# I2C_Switch.net
KiCad netlist of a schematic drawn in Altium Designer
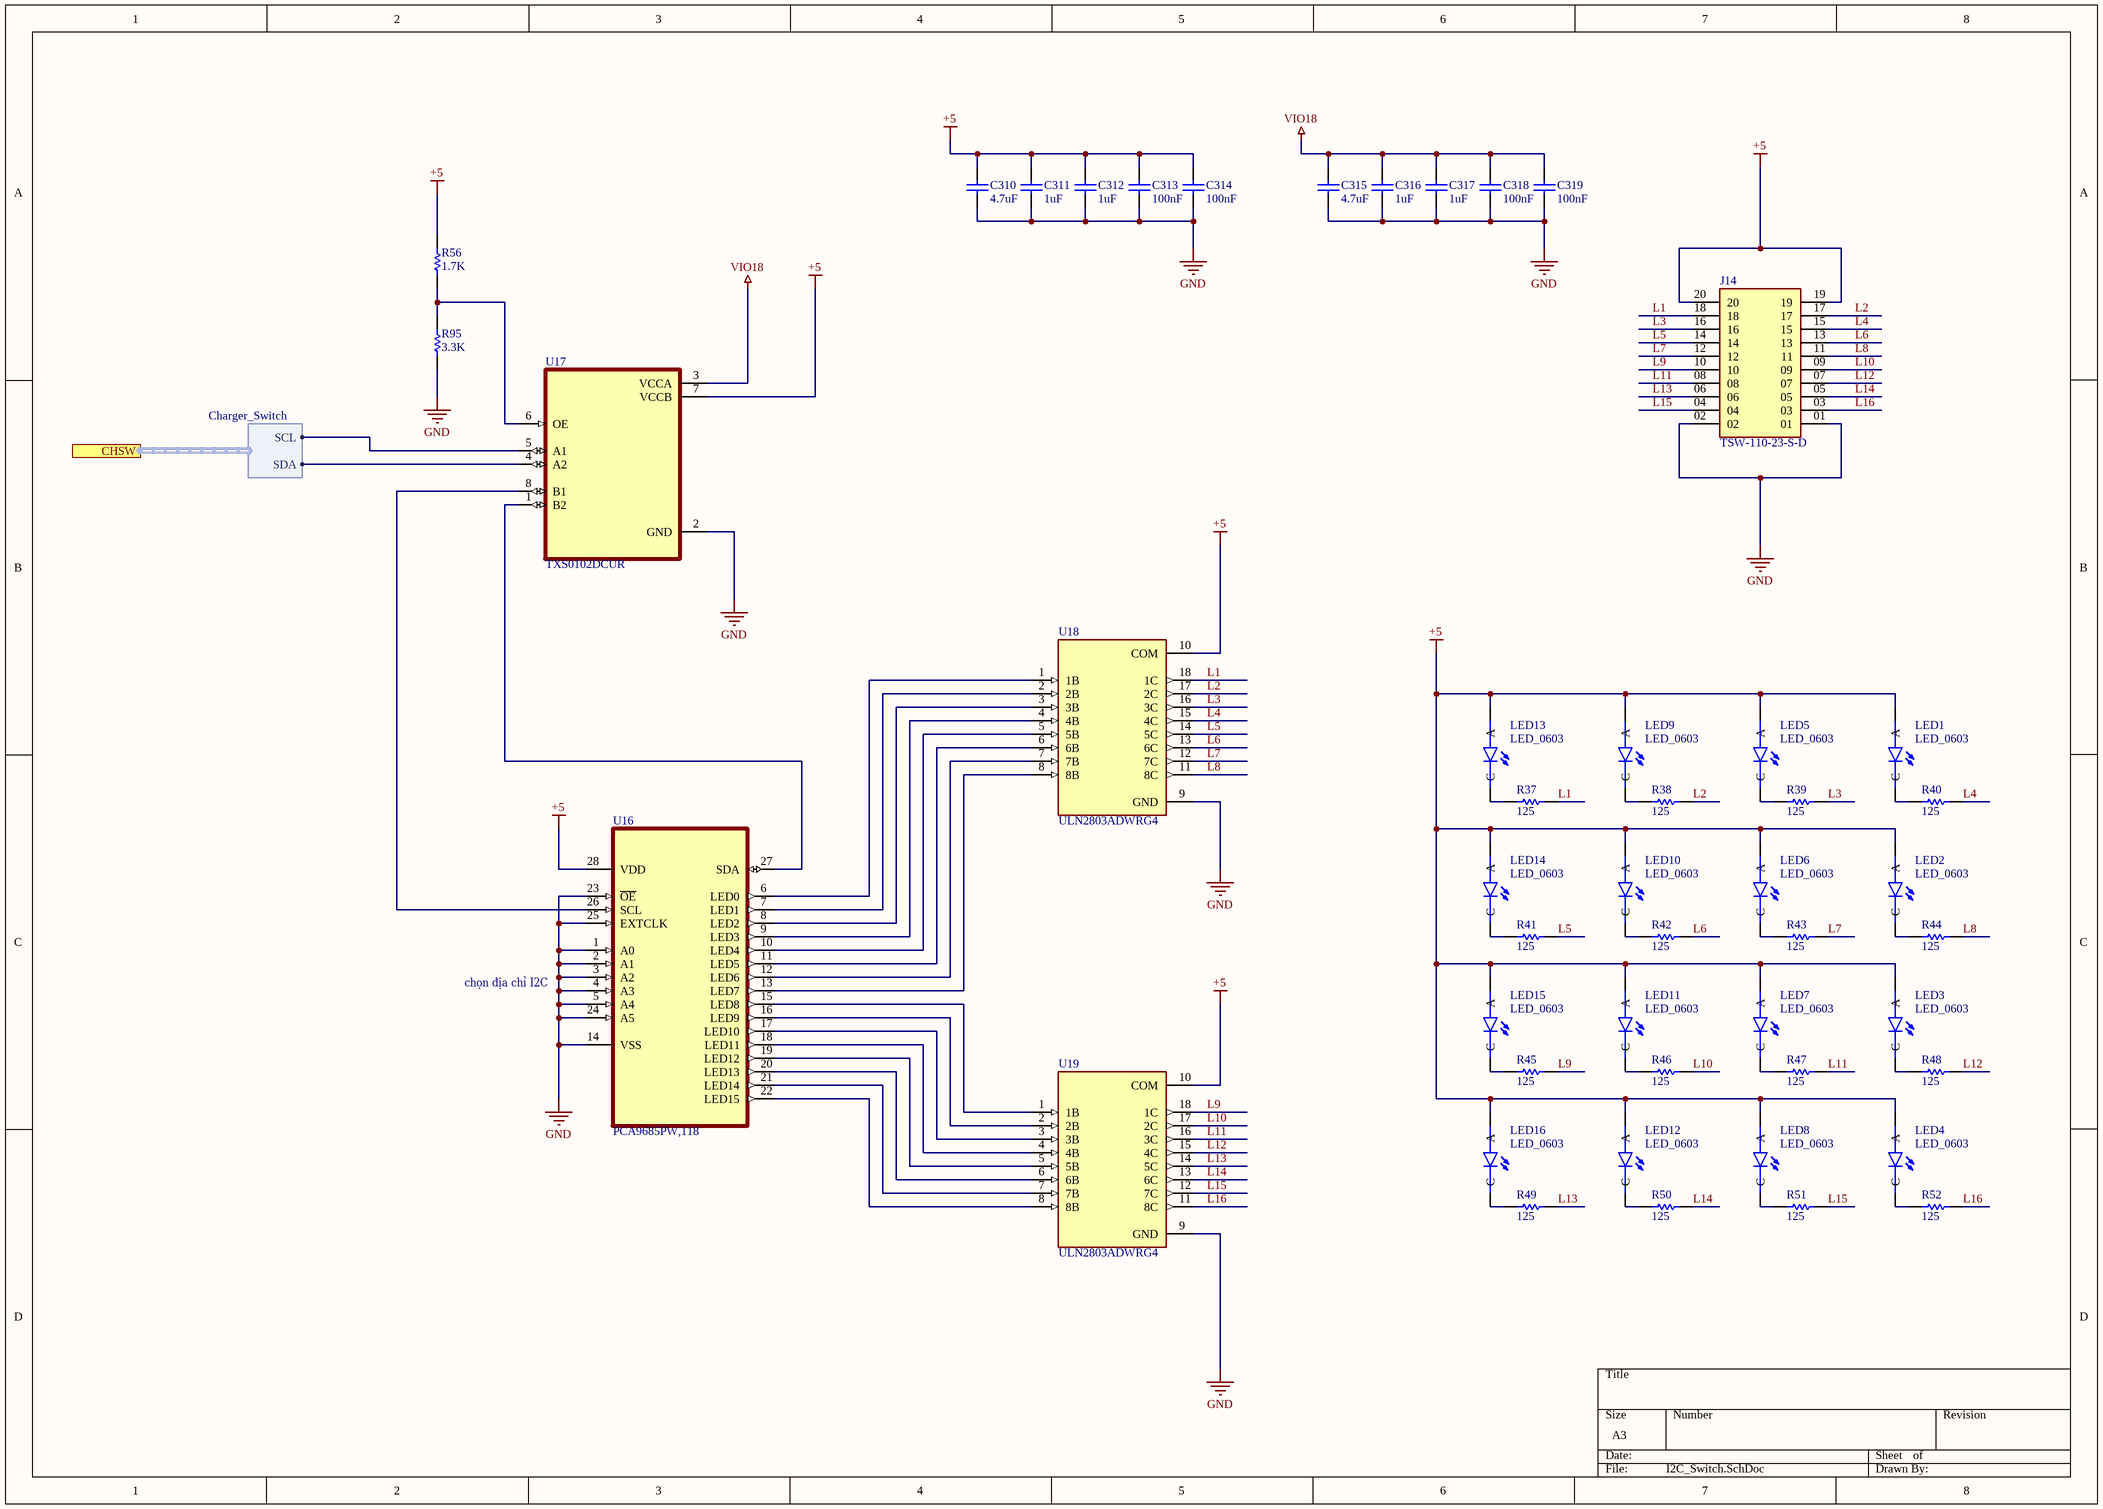
[diagram p0: I2C_Switch.SchDoc]

(export (version "E")
  (design (tool "Eeschema 10.0.6"))
  (components
    (comp (ref "C310")
      (value "4.7uF")
      (footprint "C0805")
      (fields (field (name "Comment") "C0805"))
      (libsource (lib "kit") (part "C0805"))
    )
    (comp (ref "C311")
      (value "1uF")
      (footprint "C0805")
      (fields (field (name "Comment") "C0805"))
      (libsource (lib "kit") (part "C0805"))
    )
    (comp (ref "C312")
      (value "1uF")
      (footprint "C0805")
      (fields (field (name "Comment") "C0805"))
      (libsource (lib "kit") (part "C0805"))
    )
    (comp (ref "C313")
      (value "100nF")
      (footprint "C0603")
      (fields (field (name "Comment") "C0603"))
      (libsource (lib "kit") (part "C0603"))
    )
    (comp (ref "C314")
      (value "100nF")
      (footprint "C0603")
      (fields (field (name "Comment") "C0603"))
      (libsource (lib "kit") (part "C0603"))
    )
    (comp (ref "C315")
      (value "4.7uF")
      (footprint "C0805")
      (fields (field (name "Comment") "C0805"))
      (libsource (lib "kit") (part "C0805"))
    )
    (comp (ref "C316")
      (value "1uF")
      (footprint "C0805")
      (fields (field (name "Comment") "C0805"))
      (libsource (lib "kit") (part "C0805"))
    )
    (comp (ref "C317")
      (value "1uF")
      (footprint "C0805")
      (fields (field (name "Comment") "C0805"))
      (libsource (lib "kit") (part "C0805"))
    )
    (comp (ref "C318")
      (value "100nF")
      (footprint "C0603")
      (fields (field (name "Comment") "C0603"))
      (libsource (lib "kit") (part "C0603"))
    )
    (comp (ref "C319")
      (value "100nF")
      (footprint "C0603")
      (fields (field (name "Comment") "C0603"))
      (libsource (lib "kit") (part "C0603"))
    )
    (comp (ref "J14")
      (value "TSW-110-23-S-D")
      (footprint "SAMTEC_TSW-110-23-S-D")
      (description "TSW Series .100 Terminal Strip")
      (libsource (lib "kit") (part "TSW-110-23-S-D"))
    )
    (comp (ref "LED1")
      (value "LED_0603")
      (footprint "LED_0603")
      (description "LED SMD")
      (libsource (lib "kit") (part "LED_0603"))
    )
    (comp (ref "LED2")
      (value "LED_0603")
      (footprint "LED_0603")
      (description "LED SMD")
      (libsource (lib "kit") (part "LED_0603"))
    )
    (comp (ref "LED3")
      (value "LED_0603")
      (footprint "LED_0603")
      (description "LED SMD")
      (libsource (lib "kit") (part "LED_0603"))
    )
    (comp (ref "LED4")
      (value "LED_0603")
      (footprint "LED_0603")
      (description "LED SMD")
      (libsource (lib "kit") (part "LED_0603"))
    )
    (comp (ref "LED5")
      (value "LED_0603")
      (footprint "LED_0603")
      (description "LED SMD")
      (libsource (lib "kit") (part "LED_0603"))
    )
    (comp (ref "LED6")
      (value "LED_0603")
      (footprint "LED_0603")
      (description "LED SMD")
      (libsource (lib "kit") (part "LED_0603"))
    )
    (comp (ref "LED7")
      (value "LED_0603")
      (footprint "LED_0603")
      (description "LED SMD")
      (libsource (lib "kit") (part "LED_0603"))
    )
    (comp (ref "LED8")
      (value "LED_0603")
      (footprint "LED_0603")
      (description "LED SMD")
      (libsource (lib "kit") (part "LED_0603"))
    )
    (comp (ref "LED9")
      (value "LED_0603")
      (footprint "LED_0603")
      (description "LED SMD")
      (libsource (lib "kit") (part "LED_0603"))
    )
    (comp (ref "LED10")
      (value "LED_0603")
      (footprint "LED_0603")
      (description "LED SMD")
      (libsource (lib "kit") (part "LED_0603"))
    )
    (comp (ref "LED11")
      (value "LED_0603")
      (footprint "LED_0603")
      (description "LED SMD")
      (libsource (lib "kit") (part "LED_0603"))
    )
    (comp (ref "LED12")
      (value "LED_0603")
      (footprint "LED_0603")
      (description "LED SMD")
      (libsource (lib "kit") (part "LED_0603"))
    )
    (comp (ref "LED13")
      (value "LED_0603")
      (footprint "LED_0603")
      (description "LED SMD")
      (libsource (lib "kit") (part "LED_0603"))
    )
    (comp (ref "LED14")
      (value "LED_0603")
      (footprint "LED_0603")
      (description "LED SMD")
      (libsource (lib "kit") (part "LED_0603"))
    )
    (comp (ref "LED15")
      (value "LED_0603")
      (footprint "LED_0603")
      (description "LED SMD")
      (libsource (lib "kit") (part "LED_0603"))
    )
    (comp (ref "LED16")
      (value "LED_0603")
      (footprint "LED_0603")
      (description "LED SMD")
      (libsource (lib "kit") (part "LED_0603"))
    )
    (comp (ref "R37")
      (value "125")
      (footprint "R0603")
      (fields (field (name "Comment") "R0603"))
      (libsource (lib "kit") (part "R0603"))
    )
    (comp (ref "R38")
      (value "125")
      (footprint "R0603")
      (fields (field (name "Comment") "R0603"))
      (libsource (lib "kit") (part "R0603"))
    )
    (comp (ref "R39")
      (value "125")
      (footprint "R0603")
      (fields (field (name "Comment") "R0603"))
      (libsource (lib "kit") (part "R0603"))
    )
    (comp (ref "R40")
      (value "125")
      (footprint "R0603")
      (fields (field (name "Comment") "R0603"))
      (libsource (lib "kit") (part "R0603"))
    )
    (comp (ref "R41")
      (value "125")
      (footprint "R0603")
      (fields (field (name "Comment") "R0603"))
      (libsource (lib "kit") (part "R0603"))
    )
    (comp (ref "R42")
      (value "125")
      (footprint "R0603")
      (fields (field (name "Comment") "R0603"))
      (libsource (lib "kit") (part "R0603"))
    )
    (comp (ref "R43")
      (value "125")
      (footprint "R0603")
      (fields (field (name "Comment") "R0603"))
      (libsource (lib "kit") (part "R0603"))
    )
    (comp (ref "R44")
      (value "125")
      (footprint "R0603")
      (fields (field (name "Comment") "R0603"))
      (libsource (lib "kit") (part "R0603"))
    )
    (comp (ref "R45")
      (value "125")
      (footprint "R0603")
      (fields (field (name "Comment") "R0603"))
      (libsource (lib "kit") (part "R0603"))
    )
    (comp (ref "R46")
      (value "125")
      (footprint "R0603")
      (fields (field (name "Comment") "R0603"))
      (libsource (lib "kit") (part "R0603"))
    )
    (comp (ref "R47")
      (value "125")
      (footprint "R0603")
      (fields (field (name "Comment") "R0603"))
      (libsource (lib "kit") (part "R0603"))
    )
    (comp (ref "R48")
      (value "125")
      (footprint "R0603")
      (fields (field (name "Comment") "R0603"))
      (libsource (lib "kit") (part "R0603"))
    )
    (comp (ref "R49")
      (value "125")
      (footprint "R0603")
      (fields (field (name "Comment") "R0603"))
      (libsource (lib "kit") (part "R0603"))
    )
    (comp (ref "R50")
      (value "125")
      (footprint "R0603")
      (fields (field (name "Comment") "R0603"))
      (libsource (lib "kit") (part "R0603"))
    )
    (comp (ref "R51")
      (value "125")
      (footprint "R0603")
      (fields (field (name "Comment") "R0603"))
      (libsource (lib "kit") (part "R0603"))
    )
    (comp (ref "R52")
      (value "125")
      (footprint "R0603")
      (fields (field (name "Comment") "R0603"))
      (libsource (lib "kit") (part "R0603"))
    )
    (comp (ref "R56")
      (value "1.7K")
      (footprint "R0603")
      (fields (field (name "Comment") "R0603"))
      (libsource (lib "kit") (part "R0603"))
    )
    (comp (ref "R95")
      (value "3.3K")
      (footprint "R0603")
      (fields (field (name "Comment") "R0603"))
      (libsource (lib "kit") (part "R0603"))
    )
    (comp (ref "U16")
      (value "PCA9685PW,118")
      (footprint "SOP65P640X110-28N")
      (description "LED Driver IC 16 Output Linear - PWM Dimming 25mA 28-TSSOP")
      (libsource (lib "kit") (part "PCA9685PW,118"))
    )
    (comp (ref "U17")
      (value "TXS0102DCUR")
      (footprint "SOP50P310X90-8N")
      (libsource (lib "kit") (part "TXS0102DCUR"))
    )
    (comp (ref "U18")
      (value "ULN2803ADWRG4")
      (footprint "SOIC127P1030X265-18N")
      (description "50-V, 8-ch darlington array 18-SOIC -40 to 85")
      (libsource (lib "kit") (part "ULN2803ADWRG4"))
    )
    (comp (ref "U19")
      (value "ULN2803ADWRG4")
      (footprint "SOIC127P1030X265-18N")
      (description "50-V, 8-ch darlington array 18-SOIC -40 to 85")
      (libsource (lib "kit") (part "ULN2803ADWRG4"))
    )
  )
  (nets
    (net (code "2") (name "+5") (class "Default")
      (node (ref "C310") (pin "2") (pinfunction "2_2") (pintype "passive"))
      (node (ref "C311") (pin "2") (pinfunction "2_2") (pintype "passive"))
      (node (ref "C312") (pin "2") (pinfunction "2_2") (pintype "passive"))
      (node (ref "C313") (pin "2") (pinfunction "2_2") (pintype "passive"))
      (node (ref "C314") (pin "2") (pinfunction "2_2") (pintype "passive"))
      (node (ref "J14") (pin "19") (pinfunction "19_19") (pintype "passive"))
      (node (ref "J14") (pin "20") (pinfunction "20_20") (pintype "passive"))
      (node (ref "LED1") (pin "A") (pinfunction "A_A") (pintype "passive"))
      (node (ref "LED10") (pin "A") (pinfunction "A_A") (pintype "passive"))
      (node (ref "LED11") (pin "A") (pinfunction "A_A") (pintype "passive"))
      (node (ref "LED12") (pin "A") (pinfunction "A_A") (pintype "passive"))
      (node (ref "LED13") (pin "A") (pinfunction "A_A") (pintype "passive"))
      (node (ref "LED14") (pin "A") (pinfunction "A_A") (pintype "passive"))
      (node (ref "LED15") (pin "A") (pinfunction "A_A") (pintype "passive"))
      (node (ref "LED16") (pin "A") (pinfunction "A_A") (pintype "passive"))
      (node (ref "LED2") (pin "A") (pinfunction "A_A") (pintype "passive"))
      (node (ref "LED3") (pin "A") (pinfunction "A_A") (pintype "passive"))
      (node (ref "LED4") (pin "A") (pinfunction "A_A") (pintype "passive"))
      (node (ref "LED5") (pin "A") (pinfunction "A_A") (pintype "passive"))
      (node (ref "LED6") (pin "A") (pinfunction "A_A") (pintype "passive"))
      (node (ref "LED7") (pin "A") (pinfunction "A_A") (pintype "passive"))
      (node (ref "LED8") (pin "A") (pinfunction "A_A") (pintype "passive"))
      (node (ref "LED9") (pin "A") (pinfunction "A_A") (pintype "passive"))
      (node (ref "R56") (pin "2") (pinfunction "2_2") (pintype "passive"))
      (node (ref "U16") (pin "28") (pinfunction "VDD_28") (pintype "power_in"))
      (node (ref "U17") (pin "7") (pinfunction "VCCB_7") (pintype "power_in"))
      (node (ref "U18") (pin "10") (pinfunction "COM_10") (pintype "power_in"))
      (node (ref "U19") (pin "10") (pinfunction "COM_10") (pintype "power_in"))
    )
    (net (code "3") (name "/L1") (class "Default")
      (node (ref "J14") (pin "18") (pinfunction "18_18") (pintype "passive"))
      (node (ref "R37") (pin "2") (pinfunction "2_2") (pintype "passive"))
      (node (ref "U18") (pin "18") (pinfunction "1C_18") (pintype "output"))
    )
    (net (code "4") (name "/L2") (class "Default")
      (node (ref "J14") (pin "17") (pinfunction "17_17") (pintype "passive"))
      (node (ref "R38") (pin "2") (pinfunction "2_2") (pintype "passive"))
      (node (ref "U18") (pin "17") (pinfunction "2C_17") (pintype "output"))
    )
    (net (code "5") (name "/L3") (class "Default")
      (node (ref "J14") (pin "16") (pinfunction "16_16") (pintype "passive"))
      (node (ref "R39") (pin "2") (pinfunction "2_2") (pintype "passive"))
      (node (ref "U18") (pin "16") (pinfunction "3C_16") (pintype "output"))
    )
    (net (code "6") (name "/L4") (class "Default")
      (node (ref "J14") (pin "15") (pinfunction "15_15") (pintype "passive"))
      (node (ref "R40") (pin "2") (pinfunction "2_2") (pintype "passive"))
      (node (ref "U18") (pin "15") (pinfunction "4C_15") (pintype "output"))
    )
    (net (code "7") (name "/L5") (class "Default")
      (node (ref "J14") (pin "14") (pinfunction "14_14") (pintype "passive"))
      (node (ref "R41") (pin "2") (pinfunction "2_2") (pintype "passive"))
      (node (ref "U18") (pin "14") (pinfunction "5C_14") (pintype "output"))
    )
    (net (code "8") (name "/L6") (class "Default")
      (node (ref "J14") (pin "13") (pinfunction "13_13") (pintype "passive"))
      (node (ref "R42") (pin "2") (pinfunction "2_2") (pintype "passive"))
      (node (ref "U18") (pin "13") (pinfunction "6C_13") (pintype "output"))
    )
    (net (code "9") (name "/L7") (class "Default")
      (node (ref "J14") (pin "12") (pinfunction "12_12") (pintype "passive"))
      (node (ref "R43") (pin "2") (pinfunction "2_2") (pintype "passive"))
      (node (ref "U18") (pin "12") (pinfunction "7C_12") (pintype "output"))
    )
    (net (code "10") (name "/L8") (class "Default")
      (node (ref "J14") (pin "11") (pinfunction "11_11") (pintype "passive"))
      (node (ref "R44") (pin "2") (pinfunction "2_2") (pintype "passive"))
      (node (ref "U18") (pin "11") (pinfunction "8C_11") (pintype "output"))
    )
    (net (code "11") (name "/L9") (class "Default")
      (node (ref "J14") (pin "10") (pinfunction "10_10") (pintype "passive"))
      (node (ref "R45") (pin "2") (pinfunction "2_2") (pintype "passive"))
      (node (ref "U19") (pin "18") (pinfunction "1C_18") (pintype "output"))
    )
    (net (code "12") (name "/L10") (class "Default")
      (node (ref "J14") (pin "09") (pinfunction "09_09") (pintype "passive"))
      (node (ref "R46") (pin "2") (pinfunction "2_2") (pintype "passive"))
      (node (ref "U19") (pin "17") (pinfunction "2C_17") (pintype "output"))
    )
    (net (code "13") (name "/L11") (class "Default")
      (node (ref "J14") (pin "08") (pinfunction "08_08") (pintype "passive"))
      (node (ref "R47") (pin "2") (pinfunction "2_2") (pintype "passive"))
      (node (ref "U19") (pin "16") (pinfunction "3C_16") (pintype "output"))
    )
    (net (code "14") (name "/L12") (class "Default")
      (node (ref "J14") (pin "07") (pinfunction "07_07") (pintype "passive"))
      (node (ref "R48") (pin "2") (pinfunction "2_2") (pintype "passive"))
      (node (ref "U19") (pin "15") (pinfunction "4C_15") (pintype "output"))
    )
    (net (code "15") (name "/L13") (class "Default")
      (node (ref "J14") (pin "06") (pinfunction "06_06") (pintype "passive"))
      (node (ref "R49") (pin "2") (pinfunction "2_2") (pintype "passive"))
      (node (ref "U19") (pin "14") (pinfunction "5C_14") (pintype "output"))
    )
    (net (code "16") (name "/L14") (class "Default")
      (node (ref "J14") (pin "05") (pinfunction "05_05") (pintype "passive"))
      (node (ref "R50") (pin "2") (pinfunction "2_2") (pintype "passive"))
      (node (ref "U19") (pin "13") (pinfunction "6C_13") (pintype "output"))
    )
    (net (code "17") (name "/L15") (class "Default")
      (node (ref "J14") (pin "04") (pinfunction "04_04") (pintype "passive"))
      (node (ref "R51") (pin "2") (pinfunction "2_2") (pintype "passive"))
      (node (ref "U19") (pin "12") (pinfunction "7C_12") (pintype "output"))
    )
    (net (code "18") (name "/L16") (class "Default")
      (node (ref "J14") (pin "03") (pinfunction "03_03") (pintype "passive"))
      (node (ref "R52") (pin "2") (pinfunction "2_2") (pintype "passive"))
      (node (ref "U19") (pin "11") (pinfunction "8C_11") (pintype "output"))
    )
    (net (code "19") (name "/SCL") (class "Default")
      (node (ref "U17") (pin "5") (pinfunction "A1_5") (pintype "bidirectional"))
    )
    (net (code "20") (name "/SDA") (class "Default")
      (node (ref "U17") (pin "4") (pinfunction "A2_4") (pintype "bidirectional"))
    )
    (net (code "22") (name "GND") (class "Default")
      (node (ref "C310") (pin "1") (pinfunction "1_1") (pintype "passive"))
      (node (ref "C311") (pin "1") (pinfunction "1_1") (pintype "passive"))
      (node (ref "C312") (pin "1") (pinfunction "1_1") (pintype "passive"))
      (node (ref "C313") (pin "1") (pinfunction "1_1") (pintype "passive"))
      (node (ref "C314") (pin "1") (pinfunction "1_1") (pintype "passive"))
      (node (ref "C315") (pin "1") (pinfunction "1_1") (pintype "passive"))
      (node (ref "C316") (pin "1") (pinfunction "1_1") (pintype "passive"))
      (node (ref "C317") (pin "1") (pinfunction "1_1") (pintype "passive"))
      (node (ref "C318") (pin "1") (pinfunction "1_1") (pintype "passive"))
      (node (ref "C319") (pin "1") (pinfunction "1_1") (pintype "passive"))
      (node (ref "J14") (pin "01") (pinfunction "01_01") (pintype "passive"))
      (node (ref "J14") (pin "02") (pinfunction "02_02") (pintype "passive"))
      (node (ref "R95") (pin "1") (pinfunction "1_1") (pintype "passive"))
      (node (ref "U16") (pin "1") (pinfunction "A0_1") (pintype "input"))
      (node (ref "U16") (pin "14") (pinfunction "VSS_14") (pintype "passive"))
      (node (ref "U16") (pin "2") (pinfunction "A1_2") (pintype "input"))
      (node (ref "U16") (pin "23") (pinfunction "~{OE}_23") (pintype "input"))
      (node (ref "U16") (pin "24") (pinfunction "A5_24") (pintype "input"))
      (node (ref "U16") (pin "25") (pinfunction "EXTCLK_25") (pintype "input"))
      (node (ref "U16") (pin "3") (pinfunction "A2_3") (pintype "input"))
      (node (ref "U16") (pin "4") (pinfunction "A3_4") (pintype "input"))
      (node (ref "U16") (pin "5") (pinfunction "A4_5") (pintype "input"))
      (node (ref "U17") (pin "2") (pinfunction "GND_2") (pintype "power_in"))
      (node (ref "U18") (pin "9") (pinfunction "GND_9") (pintype "power_in"))
      (node (ref "U19") (pin "9") (pinfunction "GND_9") (pintype "power_in"))
    )
    (net (code "23") (name "Net-(LED1-PadC)") (class "Default")
      (node (ref "LED1") (pin "C") (pinfunction "C_C") (pintype "passive"))
      (node (ref "R40") (pin "1") (pinfunction "1_1") (pintype "passive"))
    )
    (net (code "24") (name "Net-(LED2-PadC)") (class "Default")
      (node (ref "LED2") (pin "C") (pinfunction "C_C") (pintype "passive"))
      (node (ref "R44") (pin "1") (pinfunction "1_1") (pintype "passive"))
    )
    (net (code "25") (name "Net-(LED3-PadC)") (class "Default")
      (node (ref "LED3") (pin "C") (pinfunction "C_C") (pintype "passive"))
      (node (ref "R48") (pin "1") (pinfunction "1_1") (pintype "passive"))
    )
    (net (code "26") (name "Net-(LED4-PadC)") (class "Default")
      (node (ref "LED4") (pin "C") (pinfunction "C_C") (pintype "passive"))
      (node (ref "R52") (pin "1") (pinfunction "1_1") (pintype "passive"))
    )
    (net (code "27") (name "Net-(LED5-PadC)") (class "Default")
      (node (ref "LED5") (pin "C") (pinfunction "C_C") (pintype "passive"))
      (node (ref "R39") (pin "1") (pinfunction "1_1") (pintype "passive"))
    )
    (net (code "28") (name "Net-(LED6-PadC)") (class "Default")
      (node (ref "LED6") (pin "C") (pinfunction "C_C") (pintype "passive"))
      (node (ref "R43") (pin "1") (pinfunction "1_1") (pintype "passive"))
    )
    (net (code "29") (name "Net-(LED7-PadC)") (class "Default")
      (node (ref "LED7") (pin "C") (pinfunction "C_C") (pintype "passive"))
      (node (ref "R47") (pin "1") (pinfunction "1_1") (pintype "passive"))
    )
    (net (code "30") (name "Net-(LED8-PadC)") (class "Default")
      (node (ref "LED8") (pin "C") (pinfunction "C_C") (pintype "passive"))
      (node (ref "R51") (pin "1") (pinfunction "1_1") (pintype "passive"))
    )
    (net (code "31") (name "Net-(LED9-PadC)") (class "Default")
      (node (ref "LED9") (pin "C") (pinfunction "C_C") (pintype "passive"))
      (node (ref "R38") (pin "1") (pinfunction "1_1") (pintype "passive"))
    )
    (net (code "32") (name "Net-(LED10-PadC)") (class "Default")
      (node (ref "LED10") (pin "C") (pinfunction "C_C") (pintype "passive"))
      (node (ref "R42") (pin "1") (pinfunction "1_1") (pintype "passive"))
    )
    (net (code "33") (name "Net-(LED11-PadC)") (class "Default")
      (node (ref "LED11") (pin "C") (pinfunction "C_C") (pintype "passive"))
      (node (ref "R46") (pin "1") (pinfunction "1_1") (pintype "passive"))
    )
    (net (code "34") (name "Net-(LED12-PadC)") (class "Default")
      (node (ref "LED12") (pin "C") (pinfunction "C_C") (pintype "passive"))
      (node (ref "R50") (pin "1") (pinfunction "1_1") (pintype "passive"))
    )
    (net (code "35") (name "Net-(LED13-PadC)") (class "Default")
      (node (ref "LED13") (pin "C") (pinfunction "C_C") (pintype "passive"))
      (node (ref "R37") (pin "1") (pinfunction "1_1") (pintype "passive"))
    )
    (net (code "36") (name "Net-(LED14-PadC)") (class "Default")
      (node (ref "LED14") (pin "C") (pinfunction "C_C") (pintype "passive"))
      (node (ref "R41") (pin "1") (pinfunction "1_1") (pintype "passive"))
    )
    (net (code "37") (name "Net-(LED15-PadC)") (class "Default")
      (node (ref "LED15") (pin "C") (pinfunction "C_C") (pintype "passive"))
      (node (ref "R45") (pin "1") (pinfunction "1_1") (pintype "passive"))
    )
    (net (code "38") (name "Net-(LED16-PadC)") (class "Default")
      (node (ref "LED16") (pin "C") (pinfunction "C_C") (pintype "passive"))
      (node (ref "R49") (pin "1") (pinfunction "1_1") (pintype "passive"))
    )
    (net (code "39") (name "Net-(U16-LED0)") (class "Default")
      (node (ref "U16") (pin "6") (pinfunction "LED0_6") (pintype "output"))
      (node (ref "U18") (pin "1") (pinfunction "1B_1") (pintype "input"))
    )
    (net (code "40") (name "Net-(U16-LED1)") (class "Default")
      (node (ref "U16") (pin "7") (pinfunction "LED1_7") (pintype "output"))
      (node (ref "U18") (pin "2") (pinfunction "2B_2") (pintype "input"))
    )
    (net (code "41") (name "Net-(U16-LED2)") (class "Default")
      (node (ref "U16") (pin "8") (pinfunction "LED2_8") (pintype "output"))
      (node (ref "U18") (pin "3") (pinfunction "3B_3") (pintype "input"))
    )
    (net (code "42") (name "Net-(U16-LED3)") (class "Default")
      (node (ref "U16") (pin "9") (pinfunction "LED3_9") (pintype "output"))
      (node (ref "U18") (pin "4") (pinfunction "4B_4") (pintype "input"))
    )
    (net (code "43") (name "Net-(U16-LED4)") (class "Default")
      (node (ref "U16") (pin "10") (pinfunction "LED4_10") (pintype "output"))
      (node (ref "U18") (pin "5") (pinfunction "5B_5") (pintype "input"))
    )
    (net (code "44") (name "Net-(U16-LED5)") (class "Default")
      (node (ref "U16") (pin "11") (pinfunction "LED5_11") (pintype "output"))
      (node (ref "U18") (pin "6") (pinfunction "6B_6") (pintype "input"))
    )
    (net (code "45") (name "Net-(U16-LED6)") (class "Default")
      (node (ref "U16") (pin "12") (pinfunction "LED6_12") (pintype "output"))
      (node (ref "U18") (pin "7") (pinfunction "7B_7") (pintype "input"))
    )
    (net (code "46") (name "Net-(U16-LED7)") (class "Default")
      (node (ref "U16") (pin "13") (pinfunction "LED7_13") (pintype "output"))
      (node (ref "U18") (pin "8") (pinfunction "8B_8") (pintype "input"))
    )
    (net (code "47") (name "Net-(U16-LED8)") (class "Default")
      (node (ref "U16") (pin "15") (pinfunction "LED8_15") (pintype "output"))
      (node (ref "U19") (pin "1") (pinfunction "1B_1") (pintype "input"))
    )
    (net (code "48") (name "Net-(U16-LED9)") (class "Default")
      (node (ref "U16") (pin "16") (pinfunction "LED9_16") (pintype "output"))
      (node (ref "U19") (pin "2") (pinfunction "2B_2") (pintype "input"))
    )
    (net (code "49") (name "Net-(U16-LED10)") (class "Default")
      (node (ref "U16") (pin "17") (pinfunction "LED10_17") (pintype "output"))
      (node (ref "U19") (pin "3") (pinfunction "3B_3") (pintype "input"))
    )
    (net (code "50") (name "Net-(U16-LED11)") (class "Default")
      (node (ref "U16") (pin "18") (pinfunction "LED11_18") (pintype "output"))
      (node (ref "U19") (pin "4") (pinfunction "4B_4") (pintype "input"))
    )
    (net (code "51") (name "Net-(U16-LED12)") (class "Default")
      (node (ref "U16") (pin "19") (pinfunction "LED12_19") (pintype "output"))
      (node (ref "U19") (pin "5") (pinfunction "5B_5") (pintype "input"))
    )
    (net (code "52") (name "Net-(U16-LED13)") (class "Default")
      (node (ref "U16") (pin "20") (pinfunction "LED13_20") (pintype "output"))
      (node (ref "U19") (pin "6") (pinfunction "6B_6") (pintype "input"))
    )
    (net (code "53") (name "Net-(U16-LED14)") (class "Default")
      (node (ref "U16") (pin "21") (pinfunction "LED14_21") (pintype "output"))
      (node (ref "U19") (pin "7") (pinfunction "7B_7") (pintype "input"))
    )
    (net (code "54") (name "Net-(U16-LED15)") (class "Default")
      (node (ref "U16") (pin "22") (pinfunction "LED15_22") (pintype "output"))
      (node (ref "U19") (pin "8") (pinfunction "8B_8") (pintype "input"))
    )
    (net (code "55") (name "Net-(U16-SCL)") (class "Default")
      (node (ref "U16") (pin "26") (pinfunction "SCL_26") (pintype "input"))
      (node (ref "U17") (pin "8") (pinfunction "B1_8") (pintype "bidirectional"))
    )
    (net (code "56") (name "Net-(U16-SDA)") (class "Default")
      (node (ref "U16") (pin "27") (pinfunction "SDA_27") (pintype "bidirectional"))
      (node (ref "U17") (pin "1") (pinfunction "B2_1") (pintype "bidirectional"))
    )
    (net (code "57") (name "Net-(U17-OE)") (class "Default")
      (node (ref "R56") (pin "1") (pinfunction "1_1") (pintype "passive"))
      (node (ref "R95") (pin "2") (pinfunction "2_2") (pintype "passive"))
      (node (ref "U17") (pin "6") (pinfunction "OE_6") (pintype "input"))
    )
    (net (code "58") (name "VIO18") (class "Default")
      (node (ref "C315") (pin "2") (pinfunction "2_2") (pintype "passive"))
      (node (ref "C316") (pin "2") (pinfunction "2_2") (pintype "passive"))
      (node (ref "C317") (pin "2") (pinfunction "2_2") (pintype "passive"))
      (node (ref "C318") (pin "2") (pinfunction "2_2") (pintype "passive"))
      (node (ref "C319") (pin "2") (pinfunction "2_2") (pintype "passive"))
      (node (ref "U17") (pin "3") (pinfunction "VCCA_3") (pintype "power_in"))
    )
  )
)
